# 3_3VBuck.net
KiCad netlist of a schematic drawn in Altium Designer
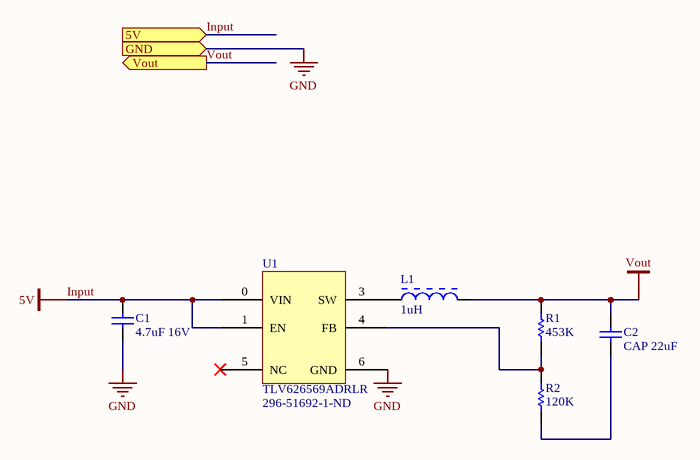
[diagram p0: 3.3VBuck.SchDoc]

(export (version "E")
  (design (tool "Eeschema 10.0.6"))
  (components
    (comp (ref "C1")
      (value "4.7uF 16V")
      (footprint "CAPC0805(2012)145_N")
      (description "CAP 4.7uF 16V ±10% 0805 (2012 Metric) Thickness 1.45mm SMD")
      (fields (field (name "TOLERANCE") "Â±10%"))
      (libsource (lib "Altium Content Vault") (part "CAP"))
    )
    (comp (ref "C2")
      (value "CAP 22uF")
      (footprint "CAPC0805(2012)100_L")
      (description "CAP 22uF 10V ±20% 0805 (2012 Metric) Thickness 1mm SMD")
      (fields (field (name "TOLERANCE") "Â±20%"))
      (libsource (lib "Altium Content Vault") (part "CAP"))
    )
    (comp (ref "L1")
      (value "1uH")
      (footprint "BOUR-SDR0403-2_V")
      (fields (field (name "MANUFACTURER") "Bourns") (field (name "PARTNUMBER") "SDR0403-1R0ML"))
      (libsource (lib "Altium Content Vault") (part "BOUR-IND-2A"))
    )
    (comp (ref "R1")
      (value "453K")
      (footprint "RESC0805(2012)_M")
      (description "453K 0.125W 1% 0805 (2012 Metric)  SMD")
      (fields (field (name "TOLERANCE") "1 %") (field (name "POWER") "0.125 W"))
      (libsource (lib "Altium Content Vault") (part "RES"))
    )
    (comp (ref "R2")
      (value "120K")
      (footprint "RESC0805(2012)_N")
      (description "120K 0.125W 5% 0805 (2012 Metric)  SMD")
      (fields (field (name "POWER") "0.125 W") (field (name "TOLERANCE") "5 %"))
      (libsource (lib "Altium Content Vault") (part "RES"))
    )
    (comp (ref "U1")
      (value "TLV626569ADRLR")
      (footprint "*SOT50P160X60-6N")
      (fields
        (field (name "MANUFACTURER") "Texas Instruments")
        (field (name "MANUFACTURER PART NUMBER") "TLV62569ADRLR")
        (field (name "SUPPLIER PART NUMBER 1") "296-51692-1-ND")
      )
      (libsource (lib "3.3V_buck") (part "TLV626569ADRLR"))
    )
  )
  (nets
    (net (code "1") (name "5V") (class "Default")
      (node (ref "C1") (pin "2") (pinfunction "2_2") (pintype "passive"))
      (node (ref "U1") (pin "0") (pinfunction "VIN_0") (pintype "passive"))
      (node (ref "U1") (pin "1") (pinfunction "EN_1") (pintype "passive"))
    )
    (net (code "2") (name "GND") (class "Default")
      (node (ref "C1") (pin "1") (pinfunction "1_1") (pintype "passive"))
      (node (ref "U1") (pin "6") (pinfunction "GND_6") (pintype "passive"))
    )
    (net (code "3") (name "Net-(C2-Pad1)") (class "Default")
      (node (ref "C2") (pin "1") (pinfunction "1_1") (pintype "passive"))
      (node (ref "R2") (pin "1") (pinfunction "1_1") (pintype "passive"))
    )
    (net (code "4") (name "Net-(U1-FB)") (class "Default")
      (node (ref "R1") (pin "1") (pinfunction "1_1") (pintype "passive"))
      (node (ref "R2") (pin "2") (pinfunction "2_2") (pintype "passive"))
      (node (ref "U1") (pin "4") (pinfunction "FB_4") (pintype "passive"))
    )
    (net (code "5") (name "Net-(U1-SW)") (class "Default")
      (node (ref "L1") (pin "1") (pinfunction "1_1") (pintype "passive"))
      (node (ref "U1") (pin "3") (pinfunction "SW_3") (pintype "passive"))
    )
    (net (code "6") (name "Vout") (class "Default")
      (node (ref "C2") (pin "2") (pinfunction "2_2") (pintype "passive"))
      (node (ref "L1") (pin "2") (pinfunction "2_2") (pintype "passive"))
      (node (ref "R1") (pin "2") (pinfunction "2_2") (pintype "passive"))
    )
    (net (code "7") (name "unconnected-(U1-NC-Pad5)") (class "Default")
      (node (ref "U1") (pin "5") (pinfunction "NC_5") (pintype "passive+no_connect"))
    )
  )
)
